# PTG.net
KiCad netlist of a schematic drawn in EAGLE
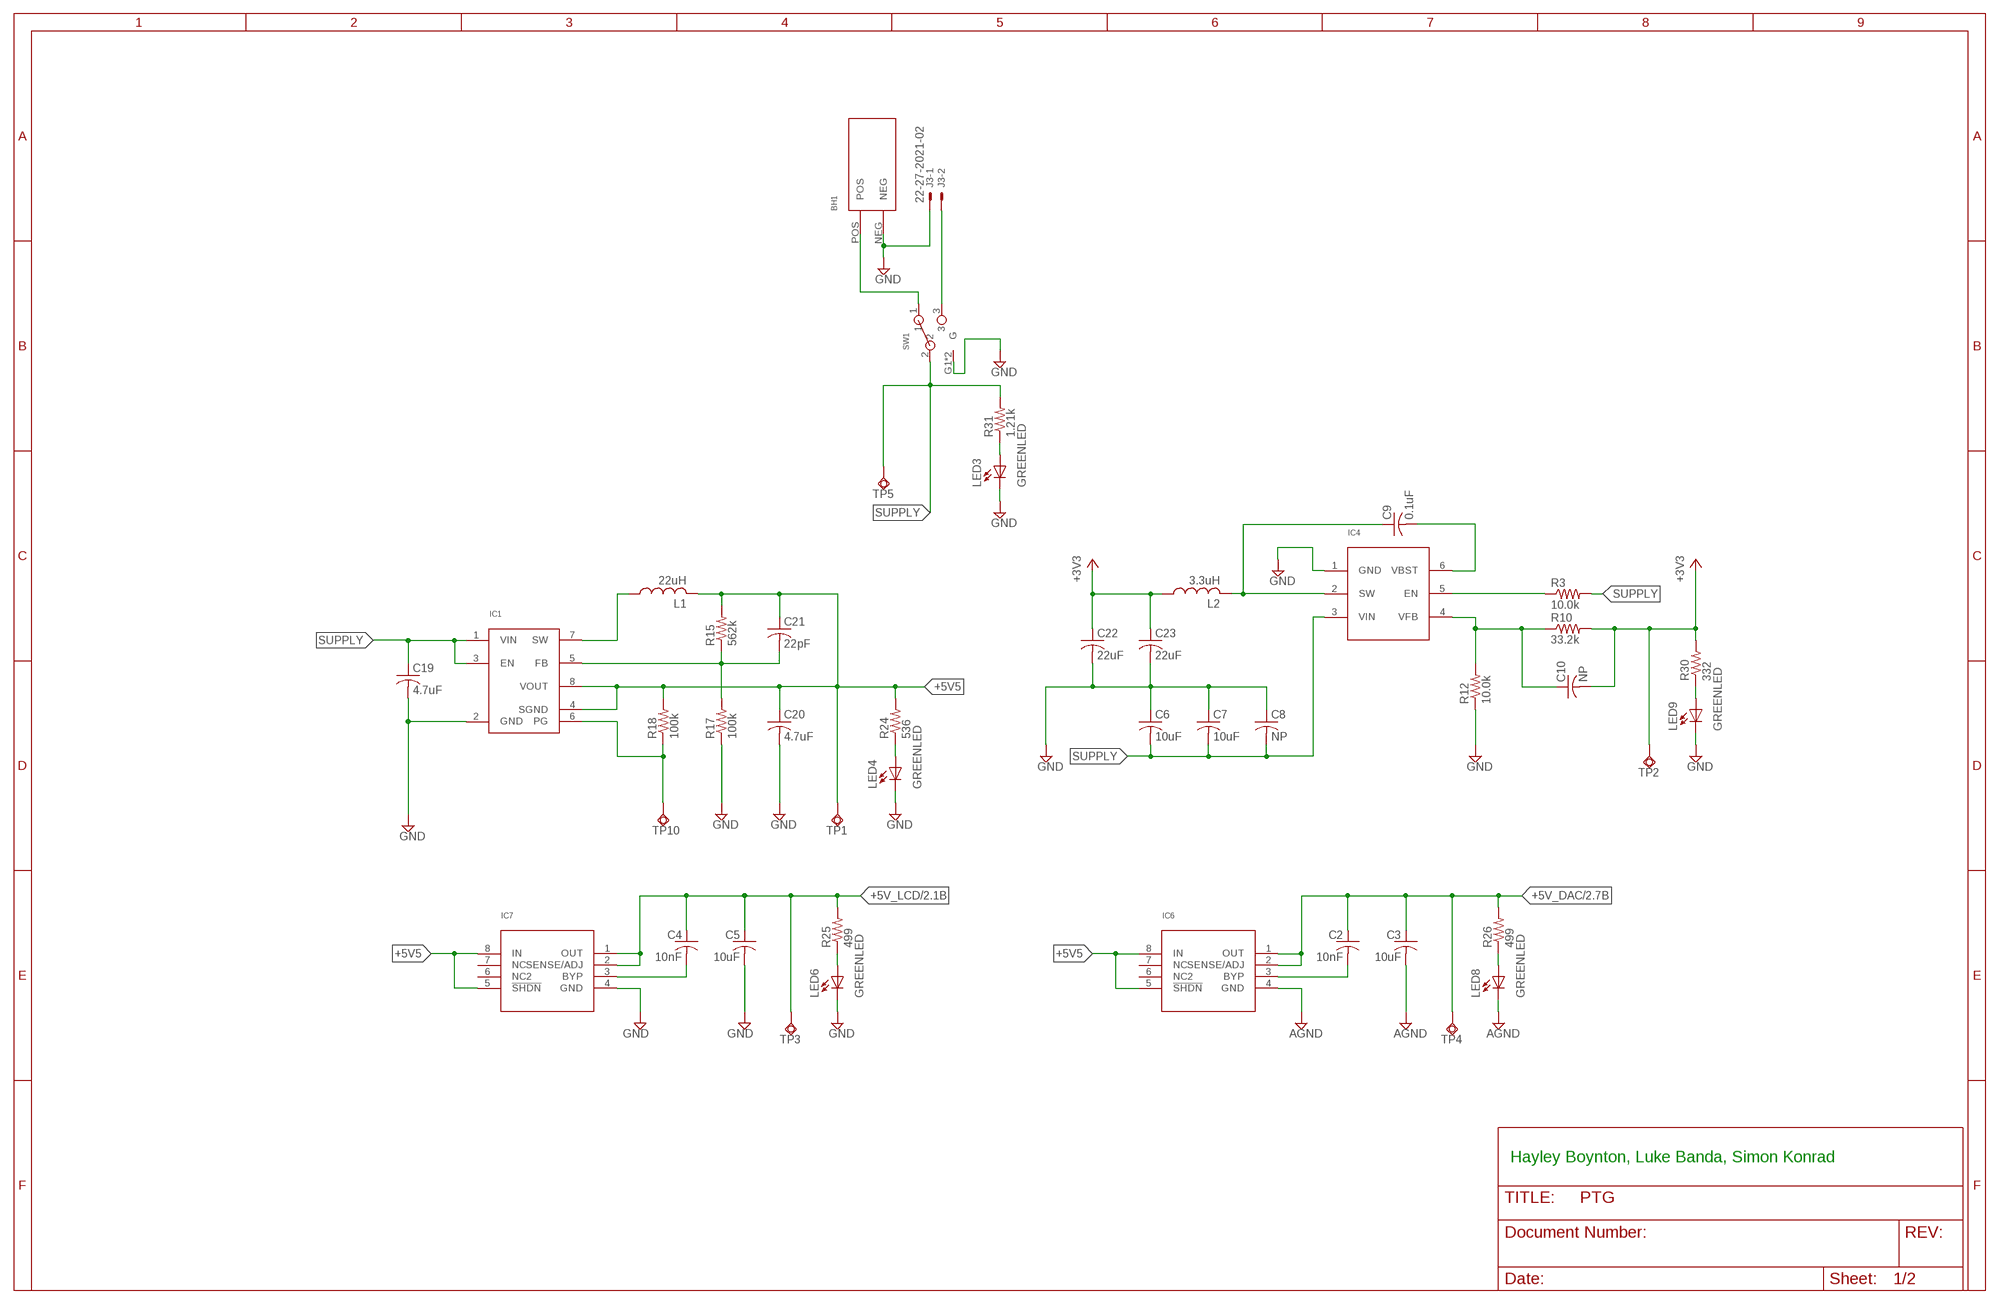
[diagram p0: schematic, sheet 1]
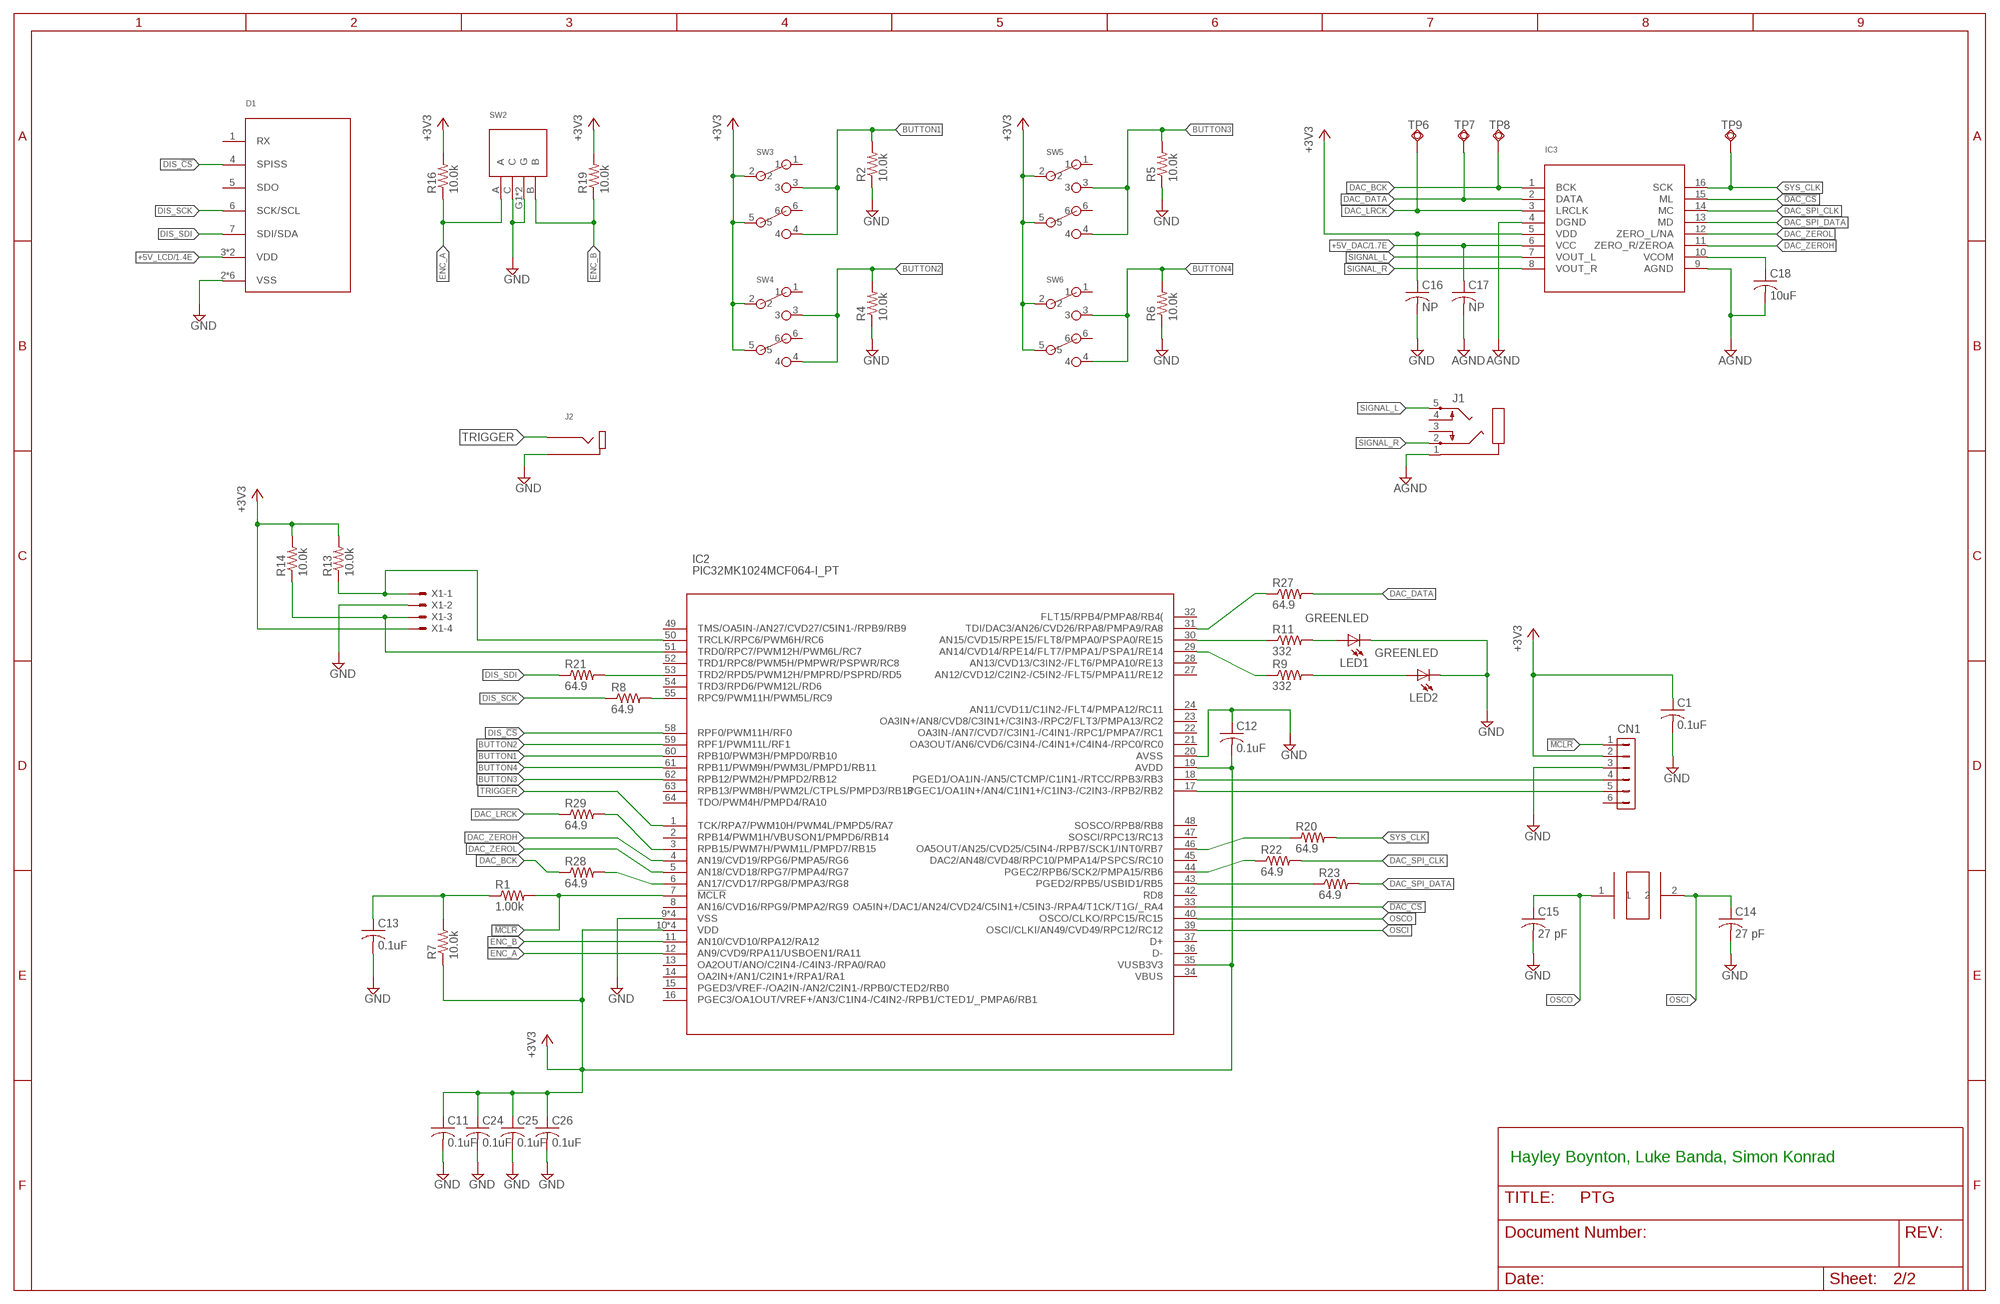
[diagram p1: schematic, sheet 2]

(export (version "E")
  (design (tool "Eeschema 10.0.6"))
  (components
    (comp (ref "C1")
      (value "0.1uF")
      (footprint "eagle-import:C0603K")
      (libsource (lib "eagle-import") (part "C-USC0603K"))
    )
    (comp (ref "C11")
      (value "0.1uF")
      (footprint "eagle-import:C0603K")
      (libsource (lib "eagle-import") (part "C-USC0603K"))
    )
    (comp (ref "C12")
      (value "0.1uF")
      (footprint "eagle-import:C0603K")
      (libsource (lib "eagle-import") (part "C-USC0603K"))
    )
    (comp (ref "C13")
      (value "0.1uF")
      (footprint "eagle-import:C0603K")
      (libsource (lib "eagle-import") (part "C-USC0603K"))
    )
    (comp (ref "C14")
      (value "27 pF")
      (footprint "eagle-import:C0603K")
      (libsource (lib "eagle-import") (part "C-USC0603K"))
    )
    (comp (ref "C15")
      (value "27 pF")
      (footprint "eagle-import:C0603K")
      (libsource (lib "eagle-import") (part "C-USC0603K"))
    )
    (comp (ref "C16")
      (value "NP")
      (footprint "eagle-import:C0603K")
      (libsource (lib "eagle-import") (part "C-USC0603K"))
    )
    (comp (ref "C17")
      (value "NP")
      (footprint "eagle-import:C0603K")
      (libsource (lib "eagle-import") (part "C-USC0603K"))
    )
    (comp (ref "C18")
      (value "10uF")
      (footprint "eagle-import:C0805K")
      (libsource (lib "eagle-import") (part "C-USC0805K"))
    )
    (comp (ref "C24")
      (value "0.1uF")
      (footprint "eagle-import:C0603K")
      (libsource (lib "eagle-import") (part "C-USC0603K"))
    )
    (comp (ref "C25")
      (value "0.1uF")
      (footprint "eagle-import:C0603K")
      (libsource (lib "eagle-import") (part "C-USC0603K"))
    )
    (comp (ref "C26")
      (value "0.1uF")
      (footprint "eagle-import:C0603K")
      (libsource (lib "eagle-import") (part "C-USC0603K"))
    )
    (comp (ref "CN1")
      (value "HDR-1X6-SIP-100")
      (footprint "eagle-import:SIP-100-6V")
      (libsource (lib "eagle-import") (part "HDR-1X6-SIP-100"))
    )
    (comp (ref "D1")
      (value "NHD-0216K3Z-GBW-V3")
      (footprint "eagle-import:NHD-0216K3Z-FL-GBW-V3")
      (libsource (lib "eagle-import") (part "NHD-0216K3Z-GBW-V3"))
    )
    (comp (ref "IC2")
      (value "PIC32MK1024MCF064-I_PT")
      (footprint "eagle-import:TQFP64-10X10")
      (libsource (lib "eagle-import") (part "PIC32MK1024MCF064-I_PT"))
    )
    (comp (ref "IC3")
      (value "PCM1748")
      (footprint "eagle-import:SSOP")
      (libsource (lib "eagle-import") (part "PCM1748"))
    )
    (comp (ref "J1")
      (value "STX31005NB")
      (footprint "eagle-import:STX31005NB")
      (libsource (lib "eagle-import") (part "STX31005NB"))
    )
    (comp (ref "J2")
      (value "RCJ-01X")
      (footprint "eagle-import:RCJ-01X")
      (libsource (lib "eagle-import") (part "RCJ-01X"))
    )
    (comp (ref "LED1")
      (value "GREENLED")
      (footprint "eagle-import:0805_10MGAP")
      (libsource (lib "eagle-import") (part "GREENLED"))
    )
    (comp (ref "LED2")
      (value "GREENLED")
      (footprint "eagle-import:0805_10MGAP")
      (libsource (lib "eagle-import") (part "GREENLED"))
    )
    (comp (ref "R1")
      (value "1.00k")
      (footprint "eagle-import:R0603")
      (libsource (lib "eagle-import") (part "resistor_R-US_R0603"))
    )
    (comp (ref "R2")
      (value "10.0k")
      (footprint "eagle-import:R0603")
      (libsource (lib "eagle-import") (part "R-US_R0603"))
    )
    (comp (ref "R4")
      (value "10.0k")
      (footprint "eagle-import:R0603")
      (libsource (lib "eagle-import") (part "R-US_R0603"))
    )
    (comp (ref "R5")
      (value "10.0k")
      (footprint "eagle-import:R0603")
      (libsource (lib "eagle-import") (part "R-US_R0603"))
    )
    (comp (ref "R6")
      (value "10.0k")
      (footprint "eagle-import:R0603")
      (libsource (lib "eagle-import") (part "R-US_R0603"))
    )
    (comp (ref "R7")
      (value "10.0k")
      (footprint "eagle-import:R0603")
      (libsource (lib "eagle-import") (part "resistor_R-US_R0603"))
    )
    (comp (ref "R8")
      (value "64.9")
      (footprint "eagle-import:R0603")
      (libsource (lib "eagle-import") (part "R-US_R0603"))
    )
    (comp (ref "R9")
      (value "332")
      (footprint "eagle-import:R0603")
      (libsource (lib "eagle-import") (part "R-US_R0603"))
    )
    (comp (ref "R11")
      (value "332")
      (footprint "eagle-import:R0603")
      (libsource (lib "eagle-import") (part "R-US_R0603"))
    )
    (comp (ref "R13")
      (value "10.0k")
      (footprint "eagle-import:R0603")
      (libsource (lib "eagle-import") (part "R-US_R0603"))
    )
    (comp (ref "R14")
      (value "10.0k")
      (footprint "eagle-import:R0603")
      (libsource (lib "eagle-import") (part "R-US_R0603"))
    )
    (comp (ref "R16")
      (value "10.0k")
      (footprint "eagle-import:R0603")
      (libsource (lib "eagle-import") (part "R-US_R0603"))
    )
    (comp (ref "R19")
      (value "10.0k")
      (footprint "eagle-import:R0603")
      (libsource (lib "eagle-import") (part "R-US_R0603"))
    )
    (comp (ref "R20")
      (value "64.9")
      (footprint "eagle-import:R0603")
      (libsource (lib "eagle-import") (part "R-US_R0603"))
    )
    (comp (ref "R21")
      (value "64.9")
      (footprint "eagle-import:R0603")
      (libsource (lib "eagle-import") (part "R-US_R0603"))
    )
    (comp (ref "R22")
      (value "64.9")
      (footprint "eagle-import:R0603")
      (libsource (lib "eagle-import") (part "R-US_R0603"))
    )
    (comp (ref "R23")
      (value "64.9")
      (footprint "eagle-import:R0603")
      (libsource (lib "eagle-import") (part "R-US_R0603"))
    )
    (comp (ref "R27")
      (value "64.9")
      (footprint "eagle-import:R0603")
      (libsource (lib "eagle-import") (part "R-US_R0603"))
    )
    (comp (ref "R28")
      (value "64.9")
      (footprint "eagle-import:R0603")
      (libsource (lib "eagle-import") (part "R-US_R0603"))
    )
    (comp (ref "R29")
      (value "64.9")
      (footprint "eagle-import:R0603")
      (libsource (lib "eagle-import") (part "R-US_R0603"))
    )
    (comp (ref "SW2")
      (value "ENCODER")
      (footprint "eagle-import:EC12E24204A7")
      (libsource (lib "eagle-import") (part "ENCODER"))
    )
    (comp (ref "SW3")
      (value "MHPS2273N")
      (footprint "eagle-import:MHPS2273N")
      (libsource (lib "eagle-import") (part "MHPS2273N"))
    )
    (comp (ref "SW4")
      (value "MHPS2273N")
      (footprint "eagle-import:MHPS2273N")
      (libsource (lib "eagle-import") (part "MHPS2273N"))
    )
    (comp (ref "SW5")
      (value "MHPS2273N")
      (footprint "eagle-import:MHPS2273N")
      (libsource (lib "eagle-import") (part "MHPS2273N"))
    )
    (comp (ref "SW6")
      (value "MHPS2273N")
      (footprint "eagle-import:MHPS2273N")
      (libsource (lib "eagle-import") (part "MHPS2273N"))
    )
    (comp (ref "TP6")
      (value "TPSQTP20SQD")
      (footprint "eagle-import:TP20SQD")
      (libsource (lib "eagle-import") (part "TPSQTP20SQD"))
    )
    (comp (ref "TP7")
      (value "TPSQTP20SQD")
      (footprint "eagle-import:TP20SQD")
      (libsource (lib "eagle-import") (part "TPSQTP20SQD"))
    )
    (comp (ref "TP8")
      (value "TPSQTP20SQD")
      (footprint "eagle-import:TP20SQD")
      (libsource (lib "eagle-import") (part "TPSQTP20SQD"))
    )
    (comp (ref "TP9")
      (value "TPSQTP20SQD")
      (footprint "eagle-import:TP20SQD")
      (libsource (lib "eagle-import") (part "TPSQTP20SQD"))
    )
    (comp (ref "X1")
      (value "22-23-2041")
      (footprint "eagle-import:22-23-2041")
      (fields (field (name "MF") "Molex"))
      (libsource (lib "eagle-import") (part "22-23-2041"))
    )
    (comp (ref "Y1")
      (value "EXTERNALCRYSTAL")
      (footprint "eagle-import:XTAL500X320X130N")
      (libsource (lib "eagle-import") (part "EXTERNALCRYSTAL"))
    )
    (comp (ref "BH1")
      (value "BATTERY_HOLDER")
      (footprint "eagle-import:BATTERY_HOLDER")
      (libsource (lib "eagle-import") (part "BATTERY_HOLDER"))
    )
    (comp (ref "C2")
      (value "10nF")
      (footprint "eagle-import:C0603K")
      (libsource (lib "eagle-import") (part "C-USC0603K"))
    )
    (comp (ref "C3")
      (value "10uF")
      (footprint "eagle-import:C0805K")
      (libsource (lib "eagle-import") (part "C-USC0805K"))
    )
    (comp (ref "C4")
      (value "10nF")
      (footprint "eagle-import:C0603K")
      (libsource (lib "eagle-import") (part "C-USC0603K"))
    )
    (comp (ref "C5")
      (value "10uF")
      (footprint "eagle-import:C0805K")
      (libsource (lib "eagle-import") (part "C-USC0805K"))
    )
    (comp (ref "C6")
      (value "10uF")
      (footprint "eagle-import:C0805K")
      (libsource (lib "eagle-import") (part "C-USC0805K"))
    )
    (comp (ref "C7")
      (value "10uF")
      (footprint "eagle-import:C0805K")
      (libsource (lib "eagle-import") (part "C-USC0805K"))
    )
    (comp (ref "C8")
      (value "NP")
      (footprint "eagle-import:C0805K")
      (libsource (lib "eagle-import") (part "C-USC0805K"))
    )
    (comp (ref "C9")
      (value "0.1uF")
      (footprint "eagle-import:C0603K")
      (libsource (lib "eagle-import") (part "C-USC0603K"))
    )
    (comp (ref "C10")
      (value "NP")
      (footprint "eagle-import:C0603K")
      (libsource (lib "eagle-import") (part "C-USC0603K"))
    )
    (comp (ref "C19")
      (value "4.7uF")
      (footprint "eagle-import:C0805K")
      (libsource (lib "eagle-import") (part "C-USC0805K"))
    )
    (comp (ref "C20")
      (value "4.7uF")
      (footprint "eagle-import:C0805K")
      (libsource (lib "eagle-import") (part "C-USC0805K"))
    )
    (comp (ref "C21")
      (value "22pF")
      (footprint "eagle-import:C0603K")
      (libsource (lib "eagle-import") (part "C-USC0603K"))
    )
    (comp (ref "C22")
      (value "22uF")
      (footprint "eagle-import:C0805K")
      (libsource (lib "eagle-import") (part "C-USC0805K"))
    )
    (comp (ref "C23")
      (value "22uF")
      (footprint "eagle-import:C0805K")
      (libsource (lib "eagle-import") (part "C-USC0805K"))
    )
    (comp (ref "IC1")
      (value "TPS62120")
      (footprint "eagle-import:SOT23(8)")
      (libsource (lib "eagle-import") (part "TPS62120"))
    )
    (comp (ref "IC4")
      (value "TPS561208")
      (footprint "eagle-import:SOT6")
      (libsource (lib "eagle-import") (part "TPS561208"))
    )
    (comp (ref "IC6")
      (value "LT1762")
      (footprint "eagle-import:MS8")
      (libsource (lib "eagle-import") (part "LT1762"))
    )
    (comp (ref "IC7")
      (value "LT1762")
      (footprint "eagle-import:MS8")
      (libsource (lib "eagle-import") (part "LT1762"))
    )
    (comp (ref "J3")
      (value "22-27-2021-02")
      (footprint "eagle-import:6410-02")
      (libsource (lib "eagle-import") (part "22-?-0227-2021"))
    )
    (comp (ref "L1")
      (value "22uH")
      (footprint "eagle-import:VLCF4020")
      (libsource (lib "eagle-import") (part "VLCF4020_INDUCTOR"))
    )
    (comp (ref "L2")
      (value "3.3uH")
      (footprint "eagle-import:VLCF4020")
      (libsource (lib "eagle-import") (part "VLCF4020_INDUCTOR"))
    )
    (comp (ref "LED3")
      (value "GREENLED")
      (footprint "eagle-import:0805_10MGAP")
      (libsource (lib "eagle-import") (part "GREENLED"))
    )
    (comp (ref "LED4")
      (value "GREENLED")
      (footprint "eagle-import:0805_10MGAP")
      (libsource (lib "eagle-import") (part "GREENLED"))
    )
    (comp (ref "LED6")
      (value "GREENLED")
      (footprint "eagle-import:0805_10MGAP")
      (libsource (lib "eagle-import") (part "GREENLED"))
    )
    (comp (ref "LED8")
      (value "GREENLED")
      (footprint "eagle-import:0805_10MGAP")
      (libsource (lib "eagle-import") (part "GREENLED"))
    )
    (comp (ref "LED9")
      (value "GREENLED")
      (footprint "eagle-import:0805_10MGAP")
      (libsource (lib "eagle-import") (part "GREENLED"))
    )
    (comp (ref "R3")
      (value "10.0k")
      (footprint "eagle-import:R0603")
      (libsource (lib "eagle-import") (part "resistor_R-US_R0603"))
    )
    (comp (ref "R10")
      (value "33.2k")
      (footprint "eagle-import:R0603")
      (libsource (lib "eagle-import") (part "resistor_R-US_R0603"))
    )
    (comp (ref "R12")
      (value "10.0k")
      (footprint "eagle-import:R0603")
      (libsource (lib "eagle-import") (part "resistor_R-US_R0603"))
    )
    (comp (ref "R15")
      (value "562k")
      (footprint "eagle-import:R0603")
      (libsource (lib "eagle-import") (part "resistor_R-US_R0603"))
    )
    (comp (ref "R17")
      (value "100k")
      (footprint "eagle-import:R0603")
      (libsource (lib "eagle-import") (part "resistor_R-US_R0603"))
    )
    (comp (ref "R18")
      (value "100k")
      (footprint "eagle-import:R0603")
      (libsource (lib "eagle-import") (part "resistor_R-US_R0603"))
    )
    (comp (ref "R24")
      (value "536")
      (footprint "eagle-import:R0603")
      (libsource (lib "eagle-import") (part "resistor_R-US_R0603"))
    )
    (comp (ref "R25")
      (value "499")
      (footprint "eagle-import:R0603")
      (libsource (lib "eagle-import") (part "resistor_R-US_R0603"))
    )
    (comp (ref "R26")
      (value "499")
      (footprint "eagle-import:R0603")
      (libsource (lib "eagle-import") (part "resistor_R-US_R0603"))
    )
    (comp (ref "R30")
      (value "332")
      (footprint "eagle-import:R0603")
      (libsource (lib "eagle-import") (part "resistor_R-US_R0603"))
    )
    (comp (ref "R31")
      (value "1.21k")
      (footprint "eagle-import:R0603")
      (libsource (lib "eagle-import") (part "resistor_R-US_R0603"))
    )
    (comp (ref "SW1")
      (value "ROCKER_SWITCH")
      (footprint "eagle-import:ROCKER_SWITCH")
      (libsource (lib "eagle-import") (part "ROCKER_SWITCH"))
    )
    (comp (ref "TP1")
      (value "TPSQTP20SQD")
      (footprint "eagle-import:TP20SQD")
      (libsource (lib "eagle-import") (part "TPSQTP20SQD"))
    )
    (comp (ref "TP2")
      (value "TPSQTP20SQD")
      (footprint "eagle-import:TP20SQD")
      (libsource (lib "eagle-import") (part "TPSQTP20SQD"))
    )
    (comp (ref "TP3")
      (value "TPSQTP20SQD")
      (footprint "eagle-import:TP20SQD")
      (libsource (lib "eagle-import") (part "TPSQTP20SQD"))
    )
    (comp (ref "TP4")
      (value "TPSQTP20SQD")
      (footprint "eagle-import:TP20SQD")
      (libsource (lib "eagle-import") (part "TPSQTP20SQD"))
    )
    (comp (ref "TP5")
      (value "TPSQTP20SQD")
      (footprint "eagle-import:TP20SQD")
      (libsource (lib "eagle-import") (part "TPSQTP20SQD"))
    )
    (comp (ref "TP10")
      (value "TPSQTP20SQD")
      (footprint "eagle-import:TP20SQD")
      (libsource (lib "eagle-import") (part "TPSQTP20SQD"))
    )
  )
  (nets
    (net (code "1") (name "+3V3") (class "Default")
      (node (ref "C1") (pin "1") (pinfunction "1_1") (pintype "passive"))
      (node (ref "C10") (pin "2") (pinfunction "2_2") (pintype "passive"))
      (node (ref "C11") (pin "1") (pinfunction "1_1") (pintype "passive"))
      (node (ref "C12") (pin "2") (pinfunction "2_2") (pintype "passive"))
      (node (ref "C16") (pin "1") (pinfunction "1_1") (pintype "passive"))
      (node (ref "C22") (pin "1") (pinfunction "1_1") (pintype "passive"))
      (node (ref "C23") (pin "1") (pinfunction "1_1") (pintype "passive"))
      (node (ref "C24") (pin "1") (pinfunction "1_1") (pintype "passive"))
      (node (ref "C25") (pin "1") (pinfunction "1_1") (pintype "passive"))
      (node (ref "C26") (pin "1") (pinfunction "1_1") (pintype "passive"))
      (node (ref "CN1") (pin "2") (pinfunction "2_2") (pintype "passive"))
      (node (ref "IC2") (pin "10") (pinfunction "VDD_10") (pintype "bidirectional"))
      (node (ref "IC2") (pin "19") (pinfunction "AVDD_19") (pintype "bidirectional"))
      (node (ref "IC2") (pin "26") (pinfunction "VDD_26") (pintype "bidirectional"))
      (node (ref "IC2") (pin "35") (pinfunction "VUSB3V3_35") (pintype "bidirectional"))
      (node (ref "IC2") (pin "38") (pinfunction "VDD_38") (pintype "bidirectional"))
      (node (ref "IC2") (pin "57") (pinfunction "VDD_57") (pintype "bidirectional"))
      (node (ref "IC3") (pin "5") (pinfunction "VDD_5") (pintype "bidirectional"))
      (node (ref "L2") (pin "1") (pinfunction "1_1") (pintype "passive"))
      (node (ref "R10") (pin "2") (pinfunction "2_2") (pintype "passive"))
      (node (ref "R13") (pin "2") (pinfunction "2_2") (pintype "passive"))
      (node (ref "R14") (pin "2") (pinfunction "2_2") (pintype "passive"))
      (node (ref "R16") (pin "2") (pinfunction "2_2") (pintype "passive"))
      (node (ref "R19") (pin "2") (pinfunction "2_2") (pintype "passive"))
      (node (ref "R30") (pin "2") (pinfunction "2_2") (pintype "passive"))
      (node (ref "R7") (pin "1") (pinfunction "1_1") (pintype "passive"))
      (node (ref "SW3") (pin "2") (pinfunction "2_2") (pintype "output"))
      (node (ref "SW3") (pin "5") (pinfunction "5_5") (pintype "output"))
      (node (ref "SW4") (pin "2") (pinfunction "2_2") (pintype "output"))
      (node (ref "SW4") (pin "5") (pinfunction "5_5") (pintype "output"))
      (node (ref "SW5") (pin "2") (pinfunction "2_2") (pintype "output"))
      (node (ref "SW5") (pin "5") (pinfunction "5_5") (pintype "output"))
      (node (ref "SW6") (pin "2") (pinfunction "2_2") (pintype "output"))
      (node (ref "SW6") (pin "5") (pinfunction "5_5") (pintype "output"))
      (node (ref "TP2") (pin "1") (pinfunction "TP_1") (pintype "input"))
      (node (ref "TP2") (pin "TP") (pinfunction "TP_TP") (pintype "input"))
      (node (ref "X1") (pin "4") (pinfunction "S_4") (pintype "passive"))
    )
    (net (code "2") (name "+5V5") (class "Default")
      (node (ref "C20") (pin "1") (pinfunction "1_1") (pintype "passive"))
      (node (ref "C21") (pin "1") (pinfunction "1_1") (pintype "passive"))
      (node (ref "IC1") (pin "4") (pinfunction "SGND_4") (pintype "bidirectional"))
      (node (ref "IC1") (pin "8") (pinfunction "VOUT_8") (pintype "bidirectional"))
      (node (ref "IC6") (pin "5") (pinfunction "~{SHDN}_5") (pintype "bidirectional"))
      (node (ref "IC6") (pin "8") (pinfunction "IN_8") (pintype "bidirectional"))
      (node (ref "IC7") (pin "5") (pinfunction "~{SHDN}_5") (pintype "bidirectional"))
      (node (ref "IC7") (pin "8") (pinfunction "IN_8") (pintype "bidirectional"))
      (node (ref "L1") (pin "2") (pinfunction "2_2") (pintype "passive"))
      (node (ref "R15") (pin "2") (pinfunction "2_2") (pintype "passive"))
      (node (ref "R18") (pin "2") (pinfunction "2_2") (pintype "passive"))
      (node (ref "R24") (pin "2") (pinfunction "2_2") (pintype "passive"))
      (node (ref "TP1") (pin "1") (pinfunction "TP_1") (pintype "input"))
      (node (ref "TP1") (pin "TP") (pinfunction "TP_TP") (pintype "input"))
    )
    (net (code "3") (name "+5V_DAC") (class "Default")
      (node (ref "C17") (pin "1") (pinfunction "1_1") (pintype "passive"))
      (node (ref "C2") (pin "1") (pinfunction "1_1") (pintype "passive"))
      (node (ref "C3") (pin "1") (pinfunction "1_1") (pintype "passive"))
      (node (ref "IC3") (pin "6") (pinfunction "VCC_6") (pintype "bidirectional"))
      (node (ref "IC6") (pin "1") (pinfunction "OUT_1") (pintype "bidirectional"))
      (node (ref "IC6") (pin "2") (pinfunction "SENSE/ADJ_2") (pintype "bidirectional"))
      (node (ref "R26") (pin "2") (pinfunction "2_2") (pintype "passive"))
      (node (ref "TP4") (pin "1") (pinfunction "TP_1") (pintype "input"))
      (node (ref "TP4") (pin "TP") (pinfunction "TP_TP") (pintype "input"))
    )
    (net (code "4") (name "+5V_LCD") (class "Default")
      (node (ref "C4") (pin "1") (pinfunction "1_1") (pintype "passive"))
      (node (ref "C5") (pin "1") (pinfunction "1_1") (pintype "passive"))
      (node (ref "D1") (pin "3") (pinfunction "VDD_3") (pintype "bidirectional"))
      (node (ref "D1") (pin "9") (pinfunction "VDD_9") (pintype "bidirectional"))
      (node (ref "IC7") (pin "1") (pinfunction "OUT_1") (pintype "bidirectional"))
      (node (ref "IC7") (pin "2") (pinfunction "SENSE/ADJ_2") (pintype "bidirectional"))
      (node (ref "R25") (pin "2") (pinfunction "2_2") (pintype "passive"))
      (node (ref "TP3") (pin "1") (pinfunction "TP_1") (pintype "input"))
      (node (ref "TP3") (pin "TP") (pinfunction "TP_TP") (pintype "input"))
    )
    (net (code "5") (name "AGND") (class "Default")
      (node (ref "C17") (pin "2") (pinfunction "2_2") (pintype "passive"))
      (node (ref "C18") (pin "2") (pinfunction "2_2") (pintype "passive"))
      (node (ref "C3") (pin "2") (pinfunction "2_2") (pintype "passive"))
      (node (ref "IC3") (pin "4") (pinfunction "DGND_4") (pintype "bidirectional"))
      (node (ref "IC3") (pin "9") (pinfunction "AGND_9") (pintype "bidirectional"))
      (node (ref "IC6") (pin "4") (pinfunction "GND_4") (pintype "bidirectional"))
      (node (ref "J1") (pin "1") (pinfunction "1_1") (pintype "passive"))
      (node (ref "LED8") (pin "1") (pinfunction "-_1") (pintype "passive"))
    )
    (net (code "6") (name "BUTTON1") (class "Default")
      (node (ref "IC2") (pin "60") (pinfunction "RPB10/PWM3H/PMPD0/RB10_60") (pintype "bidirectional"))
      (node (ref "R2") (pin "2") (pinfunction "2_2") (pintype "passive"))
      (node (ref "SW3") (pin "3") (pinfunction "3_3") (pintype "input"))
      (node (ref "SW3") (pin "4") (pinfunction "4_4") (pintype "input"))
    )
    (net (code "7") (name "BUTTON2") (class "Default")
      (node (ref "IC2") (pin "59") (pinfunction "RPF1/PWM11L/RF1_59") (pintype "bidirectional"))
      (node (ref "R4") (pin "2") (pinfunction "2_2") (pintype "passive"))
      (node (ref "SW4") (pin "3") (pinfunction "3_3") (pintype "input"))
      (node (ref "SW4") (pin "4") (pinfunction "4_4") (pintype "input"))
    )
    (net (code "8") (name "BUTTON3") (class "Default")
      (node (ref "IC2") (pin "62") (pinfunction "RPB12/PWM2H/PMPD2/RB12_62") (pintype "bidirectional"))
      (node (ref "R5") (pin "2") (pinfunction "2_2") (pintype "passive"))
      (node (ref "SW5") (pin "3") (pinfunction "3_3") (pintype "input"))
      (node (ref "SW5") (pin "4") (pinfunction "4_4") (pintype "input"))
    )
    (net (code "9") (name "BUTTON4") (class "Default")
      (node (ref "IC2") (pin "61") (pinfunction "RPB11/PWM9H/PWM3L/PMPD1/RB11_61") (pintype "bidirectional"))
      (node (ref "R6") (pin "2") (pinfunction "2_2") (pintype "passive"))
      (node (ref "SW6") (pin "3") (pinfunction "3_3") (pintype "input"))
      (node (ref "SW6") (pin "4") (pinfunction "4_4") (pintype "input"))
    )
    (net (code "10") (name "DAC_BCK") (class "Default")
      (node (ref "IC3") (pin "1") (pinfunction "BCK_1") (pintype "bidirectional"))
      (node (ref "R28") (pin "1") (pinfunction "1_1") (pintype "passive"))
      (node (ref "TP8") (pin "1") (pinfunction "TP_1") (pintype "input"))
      (node (ref "TP8") (pin "TP") (pinfunction "TP_TP") (pintype "input"))
    )
    (net (code "11") (name "DAC_DATA") (class "Default")
      (node (ref "IC3") (pin "2") (pinfunction "DATA_2") (pintype "bidirectional"))
      (node (ref "R27") (pin "2") (pinfunction "2_2") (pintype "passive"))
      (node (ref "TP7") (pin "1") (pinfunction "TP_1") (pintype "input"))
      (node (ref "TP7") (pin "TP") (pinfunction "TP_TP") (pintype "input"))
    )
    (net (code "12") (name "DAC_LRCK") (class "Default")
      (node (ref "IC3") (pin "3") (pinfunction "LRCLK_3") (pintype "bidirectional"))
      (node (ref "R29") (pin "1") (pinfunction "1_1") (pintype "passive"))
      (node (ref "TP6") (pin "1") (pinfunction "TP_1") (pintype "input"))
      (node (ref "TP6") (pin "TP") (pinfunction "TP_TP") (pintype "input"))
    )
    (net (code "13") (name "DAC_SPI_CLK") (class "Default")
      (node (ref "IC3") (pin "14") (pinfunction "MC_14") (pintype "bidirectional"))
      (node (ref "R22") (pin "2") (pinfunction "2_2") (pintype "passive"))
    )
    (net (code "14") (name "DAC_SPI_DATA") (class "Default")
      (node (ref "IC3") (pin "13") (pinfunction "MD_13") (pintype "bidirectional"))
      (node (ref "R23") (pin "2") (pinfunction "2_2") (pintype "passive"))
    )
    (net (code "15") (name "DAC_ZEROH") (class "Default")
      (node (ref "IC2") (pin "4") (pinfunction "AN19/CVD19/RPG6/PMPA5/RG6_4") (pintype "bidirectional"))
      (node (ref "IC3") (pin "11") (pinfunction "ZERO_R/ZEROA_11") (pintype "bidirectional"))
    )
    (net (code "16") (name "DAC_ZEROL") (class "Default")
      (node (ref "IC2") (pin "5") (pinfunction "AN18/CVD18/RPG7/PMPA4/RG7_5") (pintype "bidirectional"))
      (node (ref "IC3") (pin "12") (pinfunction "ZERO_L/NA_12") (pintype "bidirectional"))
    )
    (net (code "17") (name "DIS_SCK") (class "Default")
      (node (ref "D1") (pin "6") (pinfunction "SCK/SCL_6") (pintype "bidirectional"))
      (node (ref "R8") (pin "1") (pinfunction "1_1") (pintype "passive"))
    )
    (net (code "18") (name "DIS_SDI") (class "Default")
      (node (ref "D1") (pin "7") (pinfunction "SDI/SDA_7") (pintype "bidirectional"))
      (node (ref "R21") (pin "1") (pinfunction "1_1") (pintype "passive"))
    )
    (net (code "19") (name "DIS_~{CS}") (class "Default")
      (node (ref "D1") (pin "4") (pinfunction "SPISS_4") (pintype "bidirectional"))
      (node (ref "IC2") (pin "58") (pinfunction "RPF0/PWM11H/RF0_58") (pintype "bidirectional"))
    )
    (net (code "20") (name "ENC_A") (class "Default")
      (node (ref "IC2") (pin "12") (pinfunction "AN9/CVD9/RPA11/USBOEN1/RA11_12") (pintype "bidirectional"))
      (node (ref "R16") (pin "1") (pinfunction "1_1") (pintype "passive"))
      (node (ref "SW2") (pin "A") (pinfunction "A_A") (pintype "bidirectional"))
    )
    (net (code "21") (name "ENC_B") (class "Default")
      (node (ref "IC2") (pin "11") (pinfunction "AN10/CVD10/RPA12/RA12_11") (pintype "bidirectional"))
      (node (ref "R19") (pin "1") (pinfunction "1_1") (pintype "passive"))
      (node (ref "SW2") (pin "B") (pinfunction "B_B") (pintype "bidirectional"))
    )
    (net (code "22") (name "GND") (class "Default")
      (node (ref "BH1") (pin "NEG") (pinfunction "NEG_NEG") (pintype "bidirectional"))
      (node (ref "C1") (pin "2") (pinfunction "2_2") (pintype "passive"))
      (node (ref "C11") (pin "2") (pinfunction "2_2") (pintype "passive"))
      (node (ref "C12") (pin "1") (pinfunction "1_1") (pintype "passive"))
      (node (ref "C13") (pin "2") (pinfunction "2_2") (pintype "passive"))
      (node (ref "C14") (pin "2") (pinfunction "2_2") (pintype "passive"))
      (node (ref "C15") (pin "2") (pinfunction "2_2") (pintype "passive"))
      (node (ref "C16") (pin "2") (pinfunction "2_2") (pintype "passive"))
      (node (ref "C19") (pin "2") (pinfunction "2_2") (pintype "passive"))
      (node (ref "C20") (pin "2") (pinfunction "2_2") (pintype "passive"))
      (node (ref "C22") (pin "2") (pinfunction "2_2") (pintype "passive"))
      (node (ref "C23") (pin "2") (pinfunction "2_2") (pintype "passive"))
      (node (ref "C24") (pin "2") (pinfunction "2_2") (pintype "passive"))
      (node (ref "C25") (pin "2") (pinfunction "2_2") (pintype "passive"))
      (node (ref "C26") (pin "2") (pinfunction "2_2") (pintype "passive"))
      (node (ref "C5") (pin "2") (pinfunction "2_2") (pintype "passive"))
      (node (ref "C6") (pin "1") (pinfunction "1_1") (pintype "passive"))
      (node (ref "C7") (pin "1") (pinfunction "1_1") (pintype "passive"))
      (node (ref "C8") (pin "1") (pinfunction "1_1") (pintype "passive"))
      (node (ref "CN1") (pin "3") (pinfunction "3_3") (pintype "passive"))
      (node (ref "D1") (pin "2") (pinfunction "VSS_2") (pintype "bidirectional"))
      (node (ref "D1") (pin "8") (pinfunction "VSS_8") (pintype "bidirectional"))
      (node (ref "D1") (pin "G1") (pinfunction "VSS_G1") (pintype "bidirectional"))
      (node (ref "D1") (pin "G2") (pinfunction "VSS_G2") (pintype "bidirectional"))
      (node (ref "D1") (pin "G3") (pinfunction "VSS_G3") (pintype "bidirectional"))
      (node (ref "D1") (pin "G4") (pinfunction "VSS_G4") (pintype "bidirectional"))
      (node (ref "IC1") (pin "2") (pinfunction "GND_2") (pintype "bidirectional"))
      (node (ref "IC2") (pin "20") (pinfunction "AVSS_20") (pintype "bidirectional"))
      (node (ref "IC2") (pin "25") (pinfunction "VSS_25") (pintype "bidirectional"))
      (node (ref "IC2") (pin "41") (pinfunction "VSS_41") (pintype "bidirectional"))
      (node (ref "IC2") (pin "56") (pinfunction "VSS_56") (pintype "bidirectional"))
      (node (ref "IC2") (pin "9") (pinfunction "VSS_9") (pintype "bidirectional"))
      (node (ref "IC4") (pin "1") (pinfunction "GND_1") (pintype "bidirectional"))
      (node (ref "IC7") (pin "4") (pinfunction "GND_4") (pintype "bidirectional"))
      (node (ref "J2") (pin "1") (pinfunction "1_1") (pintype "passive"))
      (node (ref "J2") (pin "3") (pinfunction "1_3") (pintype "passive"))
      (node (ref "J2") (pin "4") (pinfunction "1_4") (pintype "passive"))
      (node (ref "J3") (pin "1") (pinfunction "S_1") (pintype "passive"))
      (node (ref "LED1") (pin "1") (pinfunction "-_1") (pintype "passive"))
      (node (ref "LED2") (pin "1") (pinfunction "-_1") (pintype "passive"))
      (node (ref "LED3") (pin "1") (pinfunction "-_1") (pintype "passive"))
      (node (ref "LED4") (pin "1") (pinfunction "-_1") (pintype "passive"))
      (node (ref "LED6") (pin "1") (pinfunction "-_1") (pintype "passive"))
      (node (ref "LED9") (pin "1") (pinfunction "-_1") (pintype "passive"))
      (node (ref "R12") (pin "1") (pinfunction "1_1") (pintype "passive"))
      (node (ref "R17") (pin "1") (pinfunction "1_1") (pintype "passive"))
      (node (ref "R2") (pin "1") (pinfunction "1_1") (pintype "passive"))
      (node (ref "R4") (pin "1") (pinfunction "1_1") (pintype "passive"))
      (node (ref "R5") (pin "1") (pinfunction "1_1") (pintype "passive"))
      (node (ref "R6") (pin "1") (pinfunction "1_1") (pintype "passive"))
      (node (ref "SW1") (pin "G1") (pinfunction "G_G1") (pintype "bidirectional"))
      (node (ref "SW1") (pin "G2") (pinfunction "G_G2") (pintype "bidirectional"))
      (node (ref "SW2") (pin "C") (pinfunction "C_C") (pintype "bidirectional"))
      (node (ref "SW2") (pin "G1") (pinfunction "G_G1") (pintype "bidirectional"))
      (node (ref "SW2") (pin "G2") (pinfunction "G_G2") (pintype "bidirectional"))
      (node (ref "X1") (pin "2") (pinfunction "S_2") (pintype "passive"))
    )
    (net (code "23") (name "Net-(BH1-PadPOS)") (class "Default")
      (node (ref "BH1") (pin "POS") (pinfunction "POS_POS") (pintype "bidirectional"))
      (node (ref "SW1") (pin "1") (pinfunction "1_1") (pintype "input"))
    )
    (net (code "24") (name "Net-(C13-Pad1)") (class "Default")
      (node (ref "C13") (pin "1") (pinfunction "1_1") (pintype "passive"))
      (node (ref "R1") (pin "1") (pinfunction "1_1") (pintype "passive"))
      (node (ref "R7") (pin "2") (pinfunction "2_2") (pintype "passive"))
    )
    (net (code "25") (name "Net-(IC1-FB)") (class "Default")
      (node (ref "C21") (pin "2") (pinfunction "2_2") (pintype "passive"))
      (node (ref "IC1") (pin "5") (pinfunction "FB_5") (pintype "bidirectional"))
      (node (ref "R15") (pin "1") (pinfunction "1_1") (pintype "passive"))
      (node (ref "R17") (pin "2") (pinfunction "2_2") (pintype "passive"))
    )
    (net (code "26") (name "Net-(IC1-PG)") (class "Default")
      (node (ref "IC1") (pin "6") (pinfunction "PG_6") (pintype "bidirectional"))
      (node (ref "R18") (pin "1") (pinfunction "1_1") (pintype "passive"))
      (node (ref "TP10") (pin "1") (pinfunction "TP_1") (pintype "input"))
      (node (ref "TP10") (pin "TP") (pinfunction "TP_TP") (pintype "input"))
    )
    (net (code "27") (name "Net-(IC1-SW)") (class "Default")
      (node (ref "IC1") (pin "7") (pinfunction "SW_7") (pintype "bidirectional"))
      (node (ref "L1") (pin "1") (pinfunction "1_1") (pintype "passive"))
    )
    (net (code "28") (name "Net-(IC2-AN14{slash}CVD14{slash}RPE14{slash}FLT7{slash}PMPA1{slash}PSPA1{slash}RE14)") (class "Default")
      (node (ref "IC2") (pin "29") (pinfunction "AN14/CVD14/RPE14/FLT7/PMPA1/PSPA1/RE14_29") (pintype "bidirectional"))
      (node (ref "R9") (pin "1") (pinfunction "1_1") (pintype "passive"))
    )
    (net (code "29") (name "Net-(IC2-AN15{slash}CVD15{slash}RPE15{slash}FLT8{slash}PMPA0{slash}PSPA0{slash}RE15)") (class "Default")
      (node (ref "IC2") (pin "30") (pinfunction "AN15/CVD15/RPE15/FLT8/PMPA0/PSPA0/RE15_30") (pintype "bidirectional"))
      (node (ref "R11") (pin "1") (pinfunction "1_1") (pintype "passive"))
    )
    (net (code "30") (name "Net-(IC2-AN17{slash}CVD17{slash}RPG8{slash}PMPA3{slash}RG8)") (class "Default")
      (node (ref "IC2") (pin "6") (pinfunction "AN17/CVD17/RPG8/PMPA3/RG8_6") (pintype "bidirectional"))
      (node (ref "R28") (pin "2") (pinfunction "2_2") (pintype "passive"))
    )
    (net (code "31") (name "Net-(IC2-OA5OUT{slash}AN25{slash}CVD25{slash}C5IN4-{slash}RPB7{slash}SCK1{slash}INT0{slash}RB7)") (class "Default")
      (node (ref "IC2") (pin "46") (pinfunction "OA5OUT/AN25/CVD25/C5IN4-/RPB7/SCK1/INT0/RB7_46") (pintype "bidirectional"))
      (node (ref "R20") (pin "1") (pinfunction "1_1") (pintype "passive"))
    )
    (net (code "32") (name "Net-(IC2-PGEC1{slash}OA1IN+{slash}AN4{slash}C1IN1+{slash}C1IN3-{slash}C2IN3-{slash}RPB2{slash}RB2)") (class "Default")
      (node (ref "CN1") (pin "5") (pinfunction "5_5") (pintype "passive"))
      (node (ref "IC2") (pin "17") (pinfunction "PGEC1/OA1IN+/AN4/C1IN1+/C1IN3-/C2IN3-/RPB2/RB2_17") (pintype "bidirectional"))
    )
    (net (code "33") (name "Net-(IC2-PGEC2{slash}RPB6{slash}SCK2{slash}PMPA15{slash}RB6)") (class "Default")
      (node (ref "IC2") (pin "44") (pinfunction "PGEC2/RPB6/SCK2/PMPA15/RB6_44") (pintype "bidirectional"))
      (node (ref "R22") (pin "1") (pinfunction "1_1") (pintype "passive"))
    )
    (net (code "34") (name "Net-(IC2-PGED1{slash}OA1IN-{slash}AN5{slash}CTCMP{slash}C1IN1-{slash}RTCC{slash}RPB3{slash}RB3)") (class "Default")
      (node (ref "CN1") (pin "4") (pinfunction "4_4") (pintype "passive"))
      (node (ref "IC2") (pin "18") (pinfunction "PGED1/OA1IN-/AN5/CTCMP/C1IN1-/RTCC/RPB3/RB3_18") (pintype "bidirectional"))
    )
    (net (code "35") (name "Net-(IC2-PGED2{slash}RPB5{slash}USBID1{slash}RB5)") (class "Default")
      (node (ref "IC2") (pin "43") (pinfunction "PGED2/RPB5/USBID1/RB5_43") (pintype "bidirectional"))
      (node (ref "R23") (pin "1") (pinfunction "1_1") (pintype "passive"))
    )
    (net (code "36") (name "Net-(IC2-RPB15{slash}PWM7H{slash}PWM1L{slash}PMPD7{slash}RB15)") (class "Default")
      (node (ref "IC2") (pin "3") (pinfunction "RPB15/PWM7H/PWM1L/PMPD7/RB15_3") (pintype "bidirectional"))
      (node (ref "R29") (pin "2") (pinfunction "2_2") (pintype "passive"))
    )
    (net (code "37") (name "Net-(IC2-RPC9{slash}PWM11H{slash}PWM5L{slash}RC9)") (class "Default")
      (node (ref "IC2") (pin "55") (pinfunction "RPC9/PWM11H/PWM5L/RC9_55") (pintype "bidirectional"))
      (node (ref "R8") (pin "2") (pinfunction "2_2") (pintype "passive"))
    )
    (net (code "38") (name "Net-(IC2-TDI{slash}DAC3{slash}AN26{slash}CVD26{slash}RPA8{slash}PMPA9{slash}RA8)") (class "Default")
      (node (ref "IC2") (pin "31") (pinfunction "TDI/DAC3/AN26/CVD26/RPA8/PMPA9/RA8_31") (pintype "bidirectional"))
      (node (ref "R27") (pin "1") (pinfunction "1_1") (pintype "passive"))
    )
    (net (code "39") (name "Net-(IC2-TRCLK{slash}RPC6{slash}PWM6H{slash}RC6)") (class "Default")
      (node (ref "IC2") (pin "50") (pinfunction "TRCLK/RPC6/PWM6H/RC6_50") (pintype "bidirectional"))
      (node (ref "R13") (pin "1") (pinfunction "1_1") (pintype "passive"))
      (node (ref "X1") (pin "1") (pinfunction "S_1") (pintype "passive"))
    )
    (net (code "40") (name "Net-(IC2-TRD0{slash}RPC7{slash}PWM12H{slash}PWM6L{slash}RC7)") (class "Default")
      (node (ref "IC2") (pin "51") (pinfunction "TRD0/RPC7/PWM12H/PWM6L/RC7_51") (pintype "bidirectional"))
      (node (ref "R14") (pin "1") (pinfunction "1_1") (pintype "passive"))
      (node (ref "X1") (pin "3") (pinfunction "S_3") (pintype "passive"))
    )
    (net (code "41") (name "Net-(IC2-TRD2{slash}RPD5{slash}PWM12H{slash}PMPRD{slash}PSPRD{slash}RD5)") (class "Default")
      (node (ref "IC2") (pin "53") (pinfunction "TRD2/RPD5/PWM12H/PMPRD/PSPRD/RD5_53") (pintype "bidirectional"))
      (node (ref "R21") (pin "2") (pinfunction "2_2") (pintype "passive"))
    )
    (net (code "42") (name "Net-(IC3-VCOM)") (class "Default")
      (node (ref "C18") (pin "1") (pinfunction "1_1") (pintype "passive"))
      (node (ref "IC3") (pin "10") (pinfunction "VCOM_10") (pintype "bidirectional"))
    )
    (net (code "43") (name "Net-(IC4-EN)") (class "Default")
      (node (ref "IC4") (pin "5") (pinfunction "EN_5") (pintype "bidirectional"))
      (node (ref "R3") (pin "1") (pinfunction "1_1") (pintype "passive"))
    )
    (net (code "44") (name "Net-(IC4-SW)") (class "Default")
      (node (ref "C9") (pin "1") (pinfunction "1_1") (pintype "passive"))
      (node (ref "IC4") (pin "2") (pinfunction "SW_2") (pintype "bidirectional"))
      (node (ref "L2") (pin "2") (pinfunction "2_2") (pintype "passive"))
    )
    (net (code "45") (name "Net-(IC4-VBST)") (class "Default")
      (node (ref "C9") (pin "2") (pinfunction "2_2") (pintype "passive"))
      (node (ref "IC4") (pin "6") (pinfunction "VBST_6") (pintype "bidirectional"))
    )
    (net (code "46") (name "Net-(IC4-VFB)") (class "Default")
      (node (ref "C10") (pin "1") (pinfunction "1_1") (pintype "passive"))
      (node (ref "IC4") (pin "4") (pinfunction "VFB_4") (pintype "bidirectional"))
      (node (ref "R10") (pin "1") (pinfunction "1_1") (pintype "passive"))
      (node (ref "R12") (pin "2") (pinfunction "2_2") (pintype "passive"))
    )
    (net (code "47") (name "Net-(IC6-BYP)") (class "Default")
      (node (ref "C2") (pin "2") (pinfunction "2_2") (pintype "passive"))
      (node (ref "IC6") (pin "3") (pinfunction "BYP_3") (pintype "bidirectional"))
    )
    (net (code "48") (name "Net-(IC7-BYP)") (class "Default")
      (node (ref "C4") (pin "2") (pinfunction "2_2") (pintype "passive"))
      (node (ref "IC7") (pin "3") (pinfunction "BYP_3") (pintype "bidirectional"))
    )
    (net (code "49") (name "Net-(J3B-S)") (class "Default")
      (node (ref "J3") (pin "2") (pinfunction "S_2") (pintype "passive"))
      (node (ref "SW1") (pin "3") (pinfunction "3_3") (pintype "input"))
    )
    (net (code "50") (name "Net-(LED1-+)") (class "Default")
      (node (ref "LED1") (pin "2") (pinfunction "+_2") (pintype "passive"))
      (node (ref "R11") (pin "2") (pinfunction "2_2") (pintype "passive"))
    )
    (net (code "51") (name "Net-(LED2-+)") (class "Default")
      (node (ref "LED2") (pin "2") (pinfunction "+_2") (pintype "passive"))
      (node (ref "R9") (pin "2") (pinfunction "2_2") (pintype "passive"))
    )
    (net (code "52") (name "Net-(LED3-+)") (class "Default")
      (node (ref "LED3") (pin "2") (pinfunction "+_2") (pintype "passive"))
      (node (ref "R31") (pin "1") (pinfunction "1_1") (pintype "passive"))
    )
    (net (code "53") (name "Net-(LED4-+)") (class "Default")
      (node (ref "LED4") (pin "2") (pinfunction "+_2") (pintype "passive"))
      (node (ref "R24") (pin "1") (pinfunction "1_1") (pintype "passive"))
    )
    (net (code "54") (name "Net-(LED6-+)") (class "Default")
      (node (ref "LED6") (pin "2") (pinfunction "+_2") (pintype "passive"))
      (node (ref "R25") (pin "1") (pinfunction "1_1") (pintype "passive"))
    )
    (net (code "55") (name "Net-(LED8-+)") (class "Default")
      (node (ref "LED8") (pin "2") (pinfunction "+_2") (pintype "passive"))
      (node (ref "R26") (pin "1") (pinfunction "1_1") (pintype "passive"))
    )
    (net (code "56") (name "Net-(LED9-+)") (class "Default")
      (node (ref "LED9") (pin "2") (pinfunction "+_2") (pintype "passive"))
      (node (ref "R30") (pin "1") (pinfunction "1_1") (pintype "passive"))
    )
    (net (code "57") (name "OSCI") (class "Default")
      (node (ref "C14") (pin "1") (pinfunction "1_1") (pintype "passive"))
      (node (ref "IC2") (pin "39") (pinfunction "OSCI/CLKI/AN49/CVD49/RPC12/RC12_39") (pintype "bidirectional"))
      (node (ref "Y1") (pin "2") (pinfunction "2_2") (pintype "bidirectional"))
    )
    (net (code "58") (name "OSCO") (class "Default")
      (node (ref "C15") (pin "1") (pinfunction "1_1") (pintype "passive"))
      (node (ref "IC2") (pin "40") (pinfunction "OSCO/CLKO/RPC15/RC15_40") (pintype "bidirectional"))
      (node (ref "Y1") (pin "1") (pinfunction "1_1") (pintype "bidirectional"))
    )
    (net (code "59") (name "SIGNAL_L") (class "Default")
      (node (ref "IC3") (pin "7") (pinfunction "VOUT_L_7") (pintype "bidirectional"))
      (node (ref "J1") (pin "5") (pinfunction "5_5") (pintype "passive"))
    )
    (net (code "60") (name "SIGNAL_R") (class "Default")
      (node (ref "IC3") (pin "8") (pinfunction "VOUT_R_8") (pintype "bidirectional"))
      (node (ref "J1") (pin "2") (pinfunction "2_2") (pintype "passive"))
    )
    (net (code "61") (name "SUPPLY") (class "Default")
      (node (ref "C19") (pin "1") (pinfunction "1_1") (pintype "passive"))
      (node (ref "C6") (pin "2") (pinfunction "2_2") (pintype "passive"))
      (node (ref "C7") (pin "2") (pinfunction "2_2") (pintype "passive"))
      (node (ref "C8") (pin "2") (pinfunction "2_2") (pintype "passive"))
      (node (ref "IC1") (pin "1") (pinfunction "VIN_1") (pintype "bidirectional"))
      (node (ref "IC1") (pin "3") (pinfunction "EN_3") (pintype "bidirectional"))
      (node (ref "IC4") (pin "3") (pinfunction "VIN_3") (pintype "bidirectional"))
      (node (ref "R3") (pin "2") (pinfunction "2_2") (pintype "passive"))
      (node (ref "R31") (pin "2") (pinfunction "2_2") (pintype "passive"))
      (node (ref "SW1") (pin "2") (pinfunction "2_2") (pintype "output"))
      (node (ref "TP5") (pin "1") (pinfunction "TP_1") (pintype "input"))
      (node (ref "TP5") (pin "TP") (pinfunction "TP_TP") (pintype "input"))
    )
    (net (code "62") (name "SYS_CLK") (class "Default")
      (node (ref "IC3") (pin "16") (pinfunction "SCK_16") (pintype "bidirectional"))
      (node (ref "R20") (pin "2") (pinfunction "2_2") (pintype "passive"))
      (node (ref "TP9") (pin "1") (pinfunction "TP_1") (pintype "input"))
      (node (ref "TP9") (pin "TP") (pinfunction "TP_TP") (pintype "input"))
    )
    (net (code "63") (name "TRIGGER") (class "Default")
      (node (ref "IC2") (pin "1") (pinfunction "TCK/RPA7/PWM10H/PWM4L/PMPD5/RA7_1") (pintype "bidirectional"))
      (node (ref "J2") (pin "2") (pinfunction "2_2") (pintype "passive"))
    )
    (net (code "64") (name "unconnected-(CN1-Pad6)") (class "Default")
      (node (ref "CN1") (pin "6") (pinfunction "6_6") (pintype "passive"))
    )
    (net (code "65") (name "unconnected-(D1-RX-Pad1)") (class "Default")
      (node (ref "D1") (pin "1") (pinfunction "RX_1") (pintype "bidirectional"))
    )
    (net (code "66") (name "unconnected-(D1-SDO-Pad5)") (class "Default")
      (node (ref "D1") (pin "5") (pinfunction "SDO_5") (pintype "bidirectional"))
    )
    (net (code "67") (name "unconnected-(IC2-AN11{slash}CVD11{slash}C1IN2-{slash}FLT4{slash}PMPA12{slash}RC11-Pad24)") (class "Default")
      (node (ref "IC2") (pin "24") (pinfunction "AN11/CVD11/C1IN2-/FLT4/PMPA12/RC11_24") (pintype "bidirectional"))
    )
    (net (code "68") (name "unconnected-(IC2-AN12{slash}CVD12{slash}C2IN2-{slash}C5IN2-{slash}FLT5{slash}PMPA11{slash}RE12-Pad27)") (class "Default")
      (node (ref "IC2") (pin "27") (pinfunction "AN12/CVD12/C2IN2-/C5IN2-/FLT5/PMPA11/RE12_27") (pintype "bidirectional"))
    )
    (net (code "69") (name "unconnected-(IC2-AN13{slash}CVD13{slash}C3IN2-{slash}FLT6{slash}PMPA10{slash}RE13-Pad28)") (class "Default")
      (node (ref "IC2") (pin "28") (pinfunction "AN13/CVD13/C3IN2-/FLT6/PMPA10/RE13_28") (pintype "bidirectional"))
    )
    (net (code "70") (name "unconnected-(IC2-AN16{slash}CVD16{slash}RPG9{slash}PMPA2{slash}RG9-Pad8)") (class "Default")
      (node (ref "IC2") (pin "8") (pinfunction "AN16/CVD16/RPG9/PMPA2/RG9_8") (pintype "bidirectional"))
    )
    (net (code "71") (name "unconnected-(IC2-D+-Pad37)") (class "Default")
      (node (ref "IC2") (pin "37") (pinfunction "D+_37") (pintype "bidirectional"))
    )
    (net (code "72") (name "unconnected-(IC2-D--Pad36)") (class "Default")
      (node (ref "IC2") (pin "36") (pinfunction "D-_36") (pintype "bidirectional"))
    )
    (net (code "73") (name "unconnected-(IC2-DAC2{slash}AN48{slash}CVD48{slash}RPC10{slash}PMPA14{slash}PSPCS{slash}RC10-Pad45)") (class "Default")
      (node (ref "IC2") (pin "45") (pinfunction "DAC2/AN48/CVD48/RPC10/PMPA14/PSPCS/RC10_45") (pintype "bidirectional"))
    )
    (net (code "74") (name "unconnected-(IC2-FLT15{slash}RPB4{slash}PMPA8{slash}RB4(-Pad32)") (class "Default")
      (node (ref "IC2") (pin "32") (pinfunction "FLT15/RPB4/PMPA8/RB4(_32") (pintype "bidirectional"))
    )
    (net (code "75") (name "unconnected-(IC2-OA2IN+{slash}AN1{slash}C2IN1+{slash}RPA1{slash}RA1-Pad14)") (class "Default")
      (node (ref "IC2") (pin "14") (pinfunction "OA2IN+/AN1/C2IN1+/RPA1/RA1_14") (pintype "bidirectional"))
    )
    (net (code "76") (name "unconnected-(IC2-OA2OUT{slash}ANO{slash}C2IN4-{slash}C4IN3-{slash}RPA0{slash}RA0-Pad13)") (class "Default")
      (node (ref "IC2") (pin "13") (pinfunction "OA2OUT/ANO/C2IN4-/C4IN3-/RPA0/RA0_13") (pintype "bidirectional"))
    )
    (net (code "77") (name "unconnected-(IC2-OA3IN+{slash}AN8{slash}CVD8{slash}C3IN1+{slash}C3IN3-{slash}RPC2{slash}FLT3{slash}PMPA13{slash}RC2-Pad23)") (class "Default")
      (node (ref "IC2") (pin "23") (pinfunction "OA3IN+/AN8/CVD8/C3IN1+/C3IN3-/RPC2/FLT3/PMPA13/RC2_23") (pintype "bidirectional"))
    )
    (net (code "78") (name "unconnected-(IC2-OA3IN-{slash}AN7{slash}CVD7{slash}C3IN1-{slash}C4IN1-{slash}RPC1{slash}PMPA7{slash}RC1-Pad22)") (class "Default")
      (node (ref "IC2") (pin "22") (pinfunction "OA3IN-/AN7/CVD7/C3IN1-/C4IN1-/RPC1/PMPA7/RC1_22") (pintype "bidirectional"))
    )
    (net (code "79") (name "unconnected-(IC2-OA3OUT{slash}AN6{slash}CVD6{slash}C3IN4-{slash}C4IN1+{slash}C4IN4-{slash}RPC0{slash}RC0-Pad21)") (class "Default")
      (node (ref "IC2") (pin "21") (pinfunction "OA3OUT/AN6/CVD6/C3IN4-/C4IN1+/C4IN4-/RPC0/RC0_21") (pintype "bidirectional"))
    )
    (net (code "80") (name "unconnected-(IC2-PGEC3{slash}OA1OUT{slash}VREF+{slash}AN3{slash}C1IN4-{slash}C4IN2-{slash}RPB1{slash}CTED1{slash}_PMPA6{slash}RB1-Pad16)") (class "Default")
      (node (ref "IC2") (pin "16") (pinfunction "PGEC3/OA1OUT/VREF+/AN3/C1IN4-/C4IN2-/RPB1/CTED1/_PMPA6/RB1_16") (pintype "bidirectional"))
    )
    (net (code "81") (name "unconnected-(IC2-PGED3{slash}VREF-{slash}OA2IN-{slash}AN2{slash}C2IN1-{slash}RPB0{slash}CTED2{slash}RB0-Pad15)") (class "Default")
      (node (ref "IC2") (pin "15") (pinfunction "PGED3/VREF-/OA2IN-/AN2/C2IN1-/RPB0/CTED2/RB0_15") (pintype "bidirectional"))
    )
    (net (code "82") (name "unconnected-(IC2-RD8-Pad42)") (class "Default")
      (node (ref "IC2") (pin "42") (pinfunction "RD8_42") (pintype "bidirectional"))
    )
    (net (code "83") (name "unconnected-(IC2-RPB13{slash}PWM8H{slash}PWM2L{slash}CTPLS{slash}PMPD3{slash}RB13-Pad63)") (class "Default")
      (node (ref "IC2") (pin "63") (pinfunction "RPB13/PWM8H/PWM2L/CTPLS/PMPD3/RB13_63") (pintype "bidirectional"))
    )
    (net (code "84") (name "unconnected-(IC2-RPB14{slash}PWM1H{slash}VBUSON1{slash}PMPD6{slash}RB14-Pad2)") (class "Default")
      (node (ref "IC2") (pin "2") (pinfunction "RPB14/PWM1H/VBUSON1/PMPD6/RB14_2") (pintype "bidirectional"))
    )
    (net (code "85") (name "unconnected-(IC2-SOSCI{slash}RPC13{slash}RC13-Pad47)") (class "Default")
      (node (ref "IC2") (pin "47") (pinfunction "SOSCI/RPC13/RC13_47") (pintype "bidirectional"))
    )
    (net (code "86") (name "unconnected-(IC2-SOSCO{slash}RPB8{slash}RB8-Pad48)") (class "Default")
      (node (ref "IC2") (pin "48") (pinfunction "SOSCO/RPB8/RB8_48") (pintype "bidirectional"))
    )
    (net (code "87") (name "unconnected-(IC2-TDO{slash}PWM4H{slash}PMPD4{slash}RA10-Pad64)") (class "Default")
      (node (ref "IC2") (pin "64") (pinfunction "TDO/PWM4H/PMPD4/RA10_64") (pintype "bidirectional"))
    )
    (net (code "88") (name "unconnected-(IC2-TMS{slash}OA5IN-{slash}AN27{slash}CVD27{slash}C5IN1-{slash}RPB9{slash}RB9-Pad49)") (class "Default")
      (node (ref "IC2") (pin "49") (pinfunction "TMS/OA5IN-/AN27/CVD27/C5IN1-/RPB9/RB9_49") (pintype "bidirectional"))
    )
    (net (code "89") (name "unconnected-(IC2-TRD1{slash}RPC8{slash}PWM5H{slash}PMPWR{slash}PSPWR{slash}RC8-Pad52)") (class "Default")
      (node (ref "IC2") (pin "52") (pinfunction "TRD1/RPC8/PWM5H/PMPWR/PSPWR/RC8_52") (pintype "bidirectional"))
    )
    (net (code "90") (name "unconnected-(IC2-TRD3{slash}RPD6{slash}PWM12L{slash}RD6-Pad54)") (class "Default")
      (node (ref "IC2") (pin "54") (pinfunction "TRD3/RPD6/PWM12L/RD6_54") (pintype "bidirectional"))
    )
    (net (code "91") (name "unconnected-(IC2-VBUS-Pad34)") (class "Default")
      (node (ref "IC2") (pin "34") (pinfunction "VBUS_34") (pintype "bidirectional"))
    )
    (net (code "92") (name "unconnected-(IC6-NC-Pad7)") (class "Default")
      (node (ref "IC6") (pin "7") (pinfunction "NC_7") (pintype "bidirectional"))
    )
    (net (code "93") (name "unconnected-(IC6-NC2-Pad6)") (class "Default")
      (node (ref "IC6") (pin "6") (pinfunction "NC2_6") (pintype "bidirectional"))
    )
    (net (code "94") (name "unconnected-(IC7-NC-Pad7)") (class "Default")
      (node (ref "IC7") (pin "7") (pinfunction "NC_7") (pintype "bidirectional"))
    )
    (net (code "95") (name "unconnected-(IC7-NC2-Pad6)") (class "Default")
      (node (ref "IC7") (pin "6") (pinfunction "NC2_6") (pintype "bidirectional"))
    )
    (net (code "96") (name "unconnected-(J1-Pad3)") (class "Default")
      (node (ref "J1") (pin "3") (pinfunction "3_3") (pintype "passive"))
    )
    (net (code "97") (name "unconnected-(J1-Pad4)") (class "Default")
      (node (ref "J1") (pin "4") (pinfunction "4_4") (pintype "passive"))
    )
    (net (code "98") (name "unconnected-(SW3-Pad1)") (class "Default")
      (node (ref "SW3") (pin "1") (pinfunction "1_1") (pintype "input"))
    )
    (net (code "99") (name "unconnected-(SW3-Pad6)") (class "Default")
      (node (ref "SW3") (pin "6") (pinfunction "6_6") (pintype "input"))
    )
    (net (code "100") (name "unconnected-(SW4-Pad1)") (class "Default")
      (node (ref "SW4") (pin "1") (pinfunction "1_1") (pintype "input"))
    )
    (net (code "101") (name "unconnected-(SW4-Pad6)") (class "Default")
      (node (ref "SW4") (pin "6") (pinfunction "6_6") (pintype "input"))
    )
    (net (code "102") (name "unconnected-(SW5-Pad1)") (class "Default")
      (node (ref "SW5") (pin "1") (pinfunction "1_1") (pintype "input"))
    )
    (net (code "103") (name "unconnected-(SW5-Pad6)") (class "Default")
      (node (ref "SW5") (pin "6") (pinfunction "6_6") (pintype "input"))
    )
    (net (code "104") (name "unconnected-(SW6-Pad1)") (class "Default")
      (node (ref "SW6") (pin "1") (pinfunction "1_1") (pintype "input"))
    )
    (net (code "105") (name "unconnected-(SW6-Pad6)") (class "Default")
      (node (ref "SW6") (pin "6") (pinfunction "6_6") (pintype "input"))
    )
    (net (code "106") (name "~{DAC_CS}") (class "Default")
      (node (ref "IC2") (pin "33") (pinfunction "OA5IN+/DAC1/AN24/CVD24/C5IN1+/C5IN3-/RPA4/T1CK/T1G/_RA4_33") (pintype "bidirectional"))
      (node (ref "IC3") (pin "15") (pinfunction "ML_15") (pintype "bidirectional"))
    )
    (net (code "107") (name "~{MCLR}") (class "Default")
      (node (ref "CN1") (pin "1") (pinfunction "1_1") (pintype "passive"))
      (node (ref "IC2") (pin "7") (pinfunction "~{MCLR}_7") (pintype "bidirectional"))
      (node (ref "R1") (pin "2") (pinfunction "2_2") (pintype "passive"))
    )
  )
)
